# czujnik_schemat.net
KiCad netlist of a schematic drawn in EAGLE
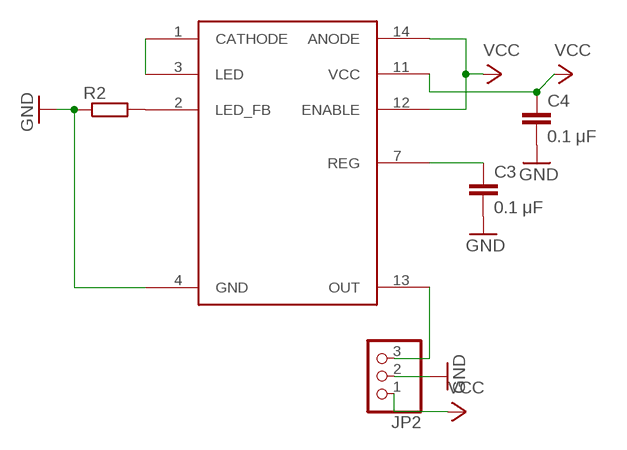
[diagram p0: schematic, sheet 1]

(export (version "E")
  (design (tool "Eeschema 10.0.6"))
  (components
    (comp (ref "C3")
      (value "0.1 μF")
      (footprint "eagle-import:C025-025X050")
      (libsource (lib "eagle-import") (part "C-EU025-025X050"))
    )
    (comp (ref "C4")
      (value "0.1 μF")
      (footprint "eagle-import:C025-025X050")
      (libsource (lib "eagle-import") (part "C-EU025-025X050"))
    )
    (comp (ref "JP2")
      (value "PINHD-1X3")
      (footprint "eagle-import:1X03")
      (libsource (lib "eagle-import") (part "PINHD-1X3"))
    )
    (comp (ref "R2")
      (value "R-EU_0204/5")
      (footprint "eagle-import:0204_5")
      (libsource (lib "eagle-import") (part "R-EU_0204/5"))
    )
    (comp (ref "U$2")
      (value "GP2Y0D810Z0F")
      (footprint "eagle-import:LP16PIN")
      (libsource (lib "eagle-import") (part "GP2Y0D810Z0F"))
    )
  )
  (nets
    (net (code "1") (name "GND") (class "Default")
      (node (ref "C3") (pin "2") (pinfunction "2_2") (pintype "passive"))
      (node (ref "C4") (pin "2") (pinfunction "2_2") (pintype "passive"))
      (node (ref "JP2") (pin "2") (pinfunction "2_2") (pintype "passive"))
      (node (ref "R2") (pin "1") (pinfunction "1_1") (pintype "passive"))
      (node (ref "U$2") (pin "4") (pinfunction "GND_4") (pintype "input"))
    )
    (net (code "2") (name "Net-(U$2-CATHODE)") (class "Default")
      (node (ref "U$2") (pin "1") (pinfunction "CATHODE_1") (pintype "input"))
      (node (ref "U$2") (pin "3") (pinfunction "LED_3") (pintype "input"))
    )
    (net (code "3") (name "Net-(U$2-LED_FB)") (class "Default")
      (node (ref "R2") (pin "2") (pinfunction "2_2") (pintype "passive"))
      (node (ref "U$2") (pin "2") (pinfunction "LED_FB_2") (pintype "input"))
    )
    (net (code "4") (name "Net-(U$2-OUT)") (class "Default")
      (node (ref "JP2") (pin "3") (pinfunction "3_3") (pintype "passive"))
      (node (ref "U$2") (pin "13") (pinfunction "OUT_13") (pintype "input"))
    )
    (net (code "5") (name "Net-(U$2-REG)") (class "Default")
      (node (ref "C3") (pin "1") (pinfunction "1_1") (pintype "passive"))
      (node (ref "U$2") (pin "7") (pinfunction "REG_7") (pintype "input"))
    )
    (net (code "6") (name "VCC") (class "Default")
      (node (ref "C4") (pin "1") (pinfunction "1_1") (pintype "passive"))
      (node (ref "JP2") (pin "1") (pinfunction "1_1") (pintype "passive"))
      (node (ref "U$2") (pin "11") (pinfunction "VCC_11") (pintype "input"))
      (node (ref "U$2") (pin "12") (pinfunction "ENABLE_12") (pintype "input"))
      (node (ref "U$2") (pin "14") (pinfunction "ANODE_14") (pintype "input"))
    )
  )
)
